# CAN.net
KiCad netlist of a schematic drawn in Altium Designer
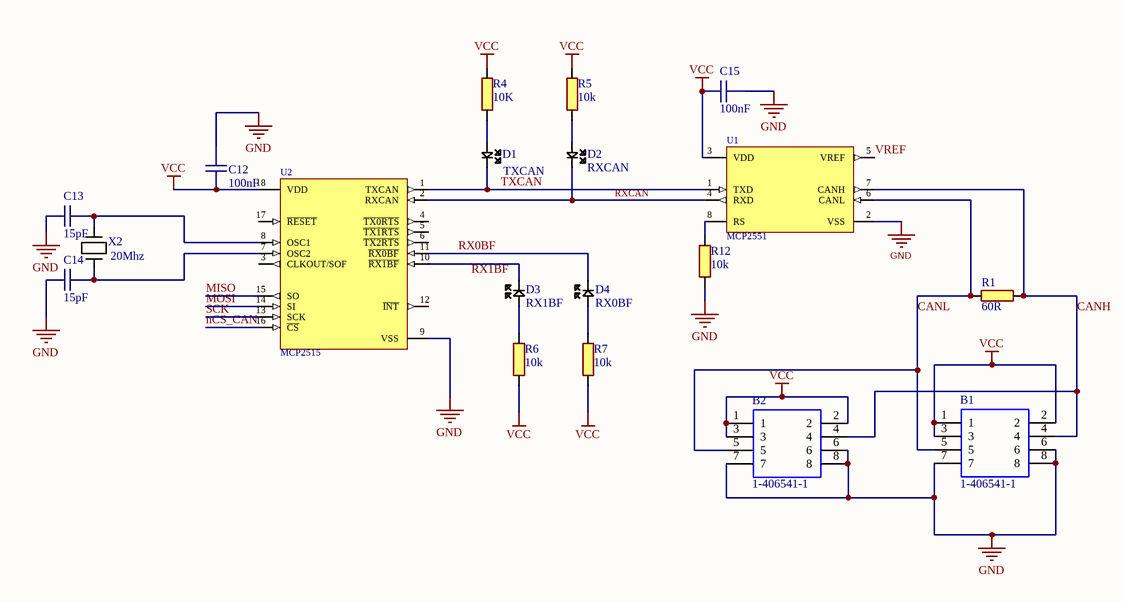
[diagram p0: CAN.SchDoc]

(export (version "E")
  (design (tool "Eeschema 10.0.6"))
  (components
    (comp (ref "B1")
      (value "1-406541-1")
      (footprint "1-406541-1_1")
      (fields (field (name "RS PART NUMBER") "2508293174"))
      (libsource (lib "1-406541-1") (part "1-406541-1"))
    )
    (comp (ref "B2")
      (value "1-406541-1")
      (footprint "1-406541-1_1")
      (fields (field (name "RS PART NUMBER") "2508293174"))
      (libsource (lib "1-406541-1") (part "1-406541-1"))
    )
    (comp (ref "C12")
      (value "100nF")
      (footprint "CAPC0603(1608)55_N")
      (description "X7R 50V 5%")
      (libsource (lib "OVLib") (part "CAP"))
    )
    (comp (ref "C13")
      (value "15pF")
      (footprint "CAPC0603(1608)55_N")
      (description "NP0 50V 5%")
      (libsource (lib "OVLib") (part "CAP"))
    )
    (comp (ref "C14")
      (value "15pF")
      (footprint "CAPC0603(1608)55_N")
      (description "NP0 50V 5%")
      (libsource (lib "OVLib") (part "CAP"))
    )
    (comp (ref "C15")
      (value "100nF")
      (footprint "CAPC0603(1608)55_N")
      (description "X7R 50V 5%")
      (libsource (lib "OVLib") (part "CAP"))
    )
    (comp (ref "D1") (value "TXCAN") (footprint "I_LEDC0603(1608)_N") (libsource (lib "OVLib") (part "LED")))
    (comp (ref "D2") (value "RXCAN") (footprint "I_LEDC0603(1608)_N") (libsource (lib "OVLib") (part "LED")))
    (comp (ref "D3") (value "RX1BF") (footprint "I_LEDC0603(1608)_N") (libsource (lib "OVLib") (part "LED")))
    (comp (ref "D4") (value "RX0BF") (footprint "I_LEDC0603(1608)_N") (libsource (lib "OVLib") (part "LED")))
    (comp (ref "R1")
      (value "60R")
      (footprint "RESC0603(1608)_N")
      (description "0.1W 1% Thick film resistor")
      (libsource (lib "") (part "Resistor2_1"))
    )
    (comp (ref "R4")
      (value "10K")
      (footprint "RESC0603(1608)_N")
      (description "0.1W 1% Thick film resistor")
      (libsource (lib "OVLib") (part "Resistor2"))
    )
    (comp (ref "R5")
      (value "10k")
      (footprint "RESC0603(1608)_N")
      (description "0.1W 1% Thick film resistor")
      (libsource (lib "OVLib") (part "Resistor2"))
    )
    (comp (ref "R6")
      (value "10k")
      (footprint "RESC0603(1608)_N")
      (description "0.1W 1% Thick film resistor")
      (libsource (lib "OVLib") (part "Resistor2"))
    )
    (comp (ref "R7")
      (value "10k")
      (footprint "RESC0603(1608)_N")
      (description "0.1W 1% Thick film resistor")
      (libsource (lib "OVLib") (part "Resistor2"))
    )
    (comp (ref "R12")
      (value "10k")
      (footprint "RESC0603(1608)_N")
      (description "0.1W 1% Thick film resistor")
      (libsource (lib "OVLib") (part "Resistor2"))
    )
    (comp (ref "U1")
      (value "MCP2551")
      (footprint "SOIC127P590X363-8N")
      (description "CAN TRANCEIVER")
      (libsource (lib "OVLib") (part "MCP2551"))
    )
    (comp (ref "U2")
      (value "MCP2515")
      (footprint "SOIC127P940X265-18N")
      (description "CAN CONTROLLER")
      (libsource (lib "OVLib") (part "MCP2515"))
    )
    (comp (ref "X2")
      (value "20Mhz")
      (footprint "CrystalTH")
      (description "20MHz")
      (libsource (lib "OVLib") (part "GENERIC-CRYSTAL"))
    )
  )
  (nets
    (net (code "1") (name "/CANH") (class "Default")
      (node (ref "B1") (pin "4") (pinfunction "4_4") (pintype "passive"))
      (node (ref "B2") (pin "4") (pinfunction "4_4") (pintype "passive"))
      (node (ref "R1") (pin "1") (pinfunction "1_1") (pintype "passive"))
      (node (ref "U1") (pin "7") (pinfunction "CANH_7") (pintype "output"))
    )
    (net (code "2") (name "/CANL") (class "Default")
      (node (ref "B1") (pin "5") (pinfunction "5_5") (pintype "passive"))
      (node (ref "B2") (pin "5") (pinfunction "5_5") (pintype "passive"))
      (node (ref "R1") (pin "2") (pinfunction "2_2") (pintype "passive"))
      (node (ref "U1") (pin "6") (pinfunction "CANL_6") (pintype "input"))
    )
    (net (code "3") (name "/MISO") (class "Default")
      (node (ref "U2") (pin "15") (pinfunction "SO_15") (pintype "output"))
    )
    (net (code "4") (name "/MOSI") (class "Default")
      (node (ref "U2") (pin "14") (pinfunction "SI_14") (pintype "input"))
    )
    (net (code "5") (name "/RX0BF") (class "Default")
      (node (ref "D4") (pin "2") (pinfunction "2_2") (pintype "passive"))
      (node (ref "U2") (pin "11") (pinfunction "~{RX0BF}_11") (pintype "input"))
    )
    (net (code "7") (name "/RXCAN") (class "Default")
      (node (ref "D2") (pin "2") (pinfunction "2_2") (pintype "passive"))
      (node (ref "U1") (pin "4") (pinfunction "RXD_4") (pintype "output"))
      (node (ref "U2") (pin "2") (pinfunction "RXCAN_2") (pintype "input"))
    )
    (net (code "8") (name "/SCK") (class "Default")
      (node (ref "U2") (pin "13") (pinfunction "SCK_13") (pintype "input"))
    )
    (net (code "9") (name "/TXCAN") (class "Default")
      (node (ref "D1") (pin "2") (pinfunction "2_2") (pintype "passive"))
      (node (ref "U1") (pin "1") (pinfunction "TXD_1") (pintype "input"))
      (node (ref "U2") (pin "1") (pinfunction "TXCAN_1") (pintype "output"))
    )
    (net (code "10") (name "/VREF") (class "Default")
      (node (ref "U1") (pin "5") (pinfunction "VREF_5") (pintype "output"))
    )
    (net (code "11") (name "/nCS_CAN") (class "Default")
      (node (ref "U2") (pin "16") (pinfunction "~{CS}_16") (pintype "input"))
    )
    (net (code "12") (name "GND") (class "Default")
      (node (ref "B1") (pin "6") (pinfunction "6_6") (pintype "passive"))
      (node (ref "B1") (pin "7") (pinfunction "7_7") (pintype "passive"))
      (node (ref "B1") (pin "8") (pinfunction "8_8") (pintype "passive"))
      (node (ref "B2") (pin "6") (pinfunction "6_6") (pintype "passive"))
      (node (ref "B2") (pin "7") (pinfunction "7_7") (pintype "passive"))
      (node (ref "B2") (pin "8") (pinfunction "8_8") (pintype "passive"))
      (node (ref "C12") (pin "1") (pinfunction "1_1") (pintype "passive"))
      (node (ref "C13") (pin "1") (pinfunction "1_1") (pintype "passive"))
      (node (ref "C14") (pin "1") (pinfunction "1_1") (pintype "passive"))
      (node (ref "C15") (pin "2") (pinfunction "2_2") (pintype "passive"))
      (node (ref "R12") (pin "1") (pinfunction "1_1") (pintype "passive"))
      (node (ref "U1") (pin "2") (pinfunction "VSS_2") (pintype "power_in"))
      (node (ref "U2") (pin "9") (pinfunction "VSS_9") (pintype "power_in"))
    )
    (net (code "13") (name "Net-(D1-Pad1)") (class "Default")
      (node (ref "D1") (pin "1") (pinfunction "1_1") (pintype "passive"))
      (node (ref "R4") (pin "1") (pinfunction "1_1") (pintype "passive"))
    )
    (net (code "14") (name "Net-(D2-Pad1)") (class "Default")
      (node (ref "D2") (pin "1") (pinfunction "1_1") (pintype "passive"))
      (node (ref "R5") (pin "1") (pinfunction "1_1") (pintype "passive"))
    )
    (net (code "15") (name "Net-(D3-Pad1)") (class "Default")
      (node (ref "D3") (pin "1") (pinfunction "1_1") (pintype "passive"))
      (node (ref "R6") (pin "2") (pinfunction "2_2") (pintype "passive"))
    )
    (net (code "16") (name "Net-(D4-Pad1)") (class "Default")
      (node (ref "D4") (pin "1") (pinfunction "1_1") (pintype "passive"))
      (node (ref "R7") (pin "2") (pinfunction "2_2") (pintype "passive"))
    )
    (net (code "17") (name "Net-(U1-RS)") (class "Default")
      (node (ref "R12") (pin "2") (pinfunction "2_2") (pintype "passive"))
      (node (ref "U1") (pin "8") (pinfunction "RS_8") (pintype "passive"))
    )
    (net (code "18") (name "Net-(U2-OSC1)") (class "Default")
      (node (ref "C13") (pin "2") (pinfunction "2_2") (pintype "passive"))
      (node (ref "U2") (pin "8") (pinfunction "OSC1_8") (pintype "input"))
      (node (ref "X2") (pin "1") (pintype "passive"))
    )
    (net (code "19") (name "Net-(U2-OSC2)") (class "Default")
      (node (ref "C14") (pin "2") (pinfunction "2_2") (pintype "passive"))
      (node (ref "U2") (pin "7") (pinfunction "OSC2_7") (pintype "input"))
      (node (ref "X2") (pin "2") (pintype "passive"))
    )
    (net (code "20") (name "Net-(U2-~{RX1BF})") (class "Default")
      (node (ref "D3") (pin "2") (pinfunction "2_2") (pintype "passive"))
      (node (ref "U2") (pin "10") (pinfunction "~{RX1BF}_10") (pintype "input"))
    )
    (net (code "21") (name "VCC") (class "Default")
      (node (ref "B1") (pin "1") (pinfunction "1_1") (pintype "passive"))
      (node (ref "B1") (pin "2") (pinfunction "2_2") (pintype "passive"))
      (node (ref "B1") (pin "3") (pinfunction "3_3") (pintype "passive"))
      (node (ref "B2") (pin "1") (pinfunction "1_1") (pintype "passive"))
      (node (ref "B2") (pin "2") (pinfunction "2_2") (pintype "passive"))
      (node (ref "B2") (pin "3") (pinfunction "3_3") (pintype "passive"))
      (node (ref "C12") (pin "2") (pinfunction "2_2") (pintype "passive"))
      (node (ref "C15") (pin "1") (pinfunction "1_1") (pintype "passive"))
      (node (ref "R4") (pin "2") (pinfunction "2_2") (pintype "passive"))
      (node (ref "R5") (pin "2") (pinfunction "2_2") (pintype "passive"))
      (node (ref "R6") (pin "1") (pinfunction "1_1") (pintype "passive"))
      (node (ref "R7") (pin "1") (pinfunction "1_1") (pintype "passive"))
      (node (ref "U1") (pin "3") (pinfunction "VDD_3") (pintype "power_in"))
      (node (ref "U2") (pin "18") (pinfunction "VDD_18") (pintype "power_in"))
    )
    (net (code "22") (name "unconnected-(U2-CLKOUT{slash}SOF-Pad3)") (class "Default")
      (node (ref "U2") (pin "3") (pinfunction "CLKOUT/SOF_3") (pintype "output"))
    )
    (net (code "23") (name "unconnected-(U2-~{INT}-Pad12)") (class "Default")
      (node (ref "U2") (pin "12") (pinfunction "~{INT}_12") (pintype "output"))
    )
    (net (code "24") (name "unconnected-(U2-~{RESET}-Pad17)") (class "Default")
      (node (ref "U2") (pin "17") (pinfunction "~{RESET}_17") (pintype "input"))
    )
    (net (code "25") (name "unconnected-(U2-~{TX0RTS}-Pad4)") (class "Default")
      (node (ref "U2") (pin "4") (pinfunction "~{TX0RTS}_4") (pintype "output"))
    )
    (net (code "26") (name "unconnected-(U2-~{TX1RTS}-Pad5)") (class "Default")
      (node (ref "U2") (pin "5") (pinfunction "~{TX1RTS}_5") (pintype "output"))
    )
    (net (code "27") (name "unconnected-(U2-~{TX2RTS}-Pad6)") (class "Default")
      (node (ref "U2") (pin "6") (pinfunction "~{TX2RTS}_6") (pintype "output"))
    )
  )
)
